# CH32V103R-R1-1v1.net
KiCad netlist of a schematic drawn in Altium Designer
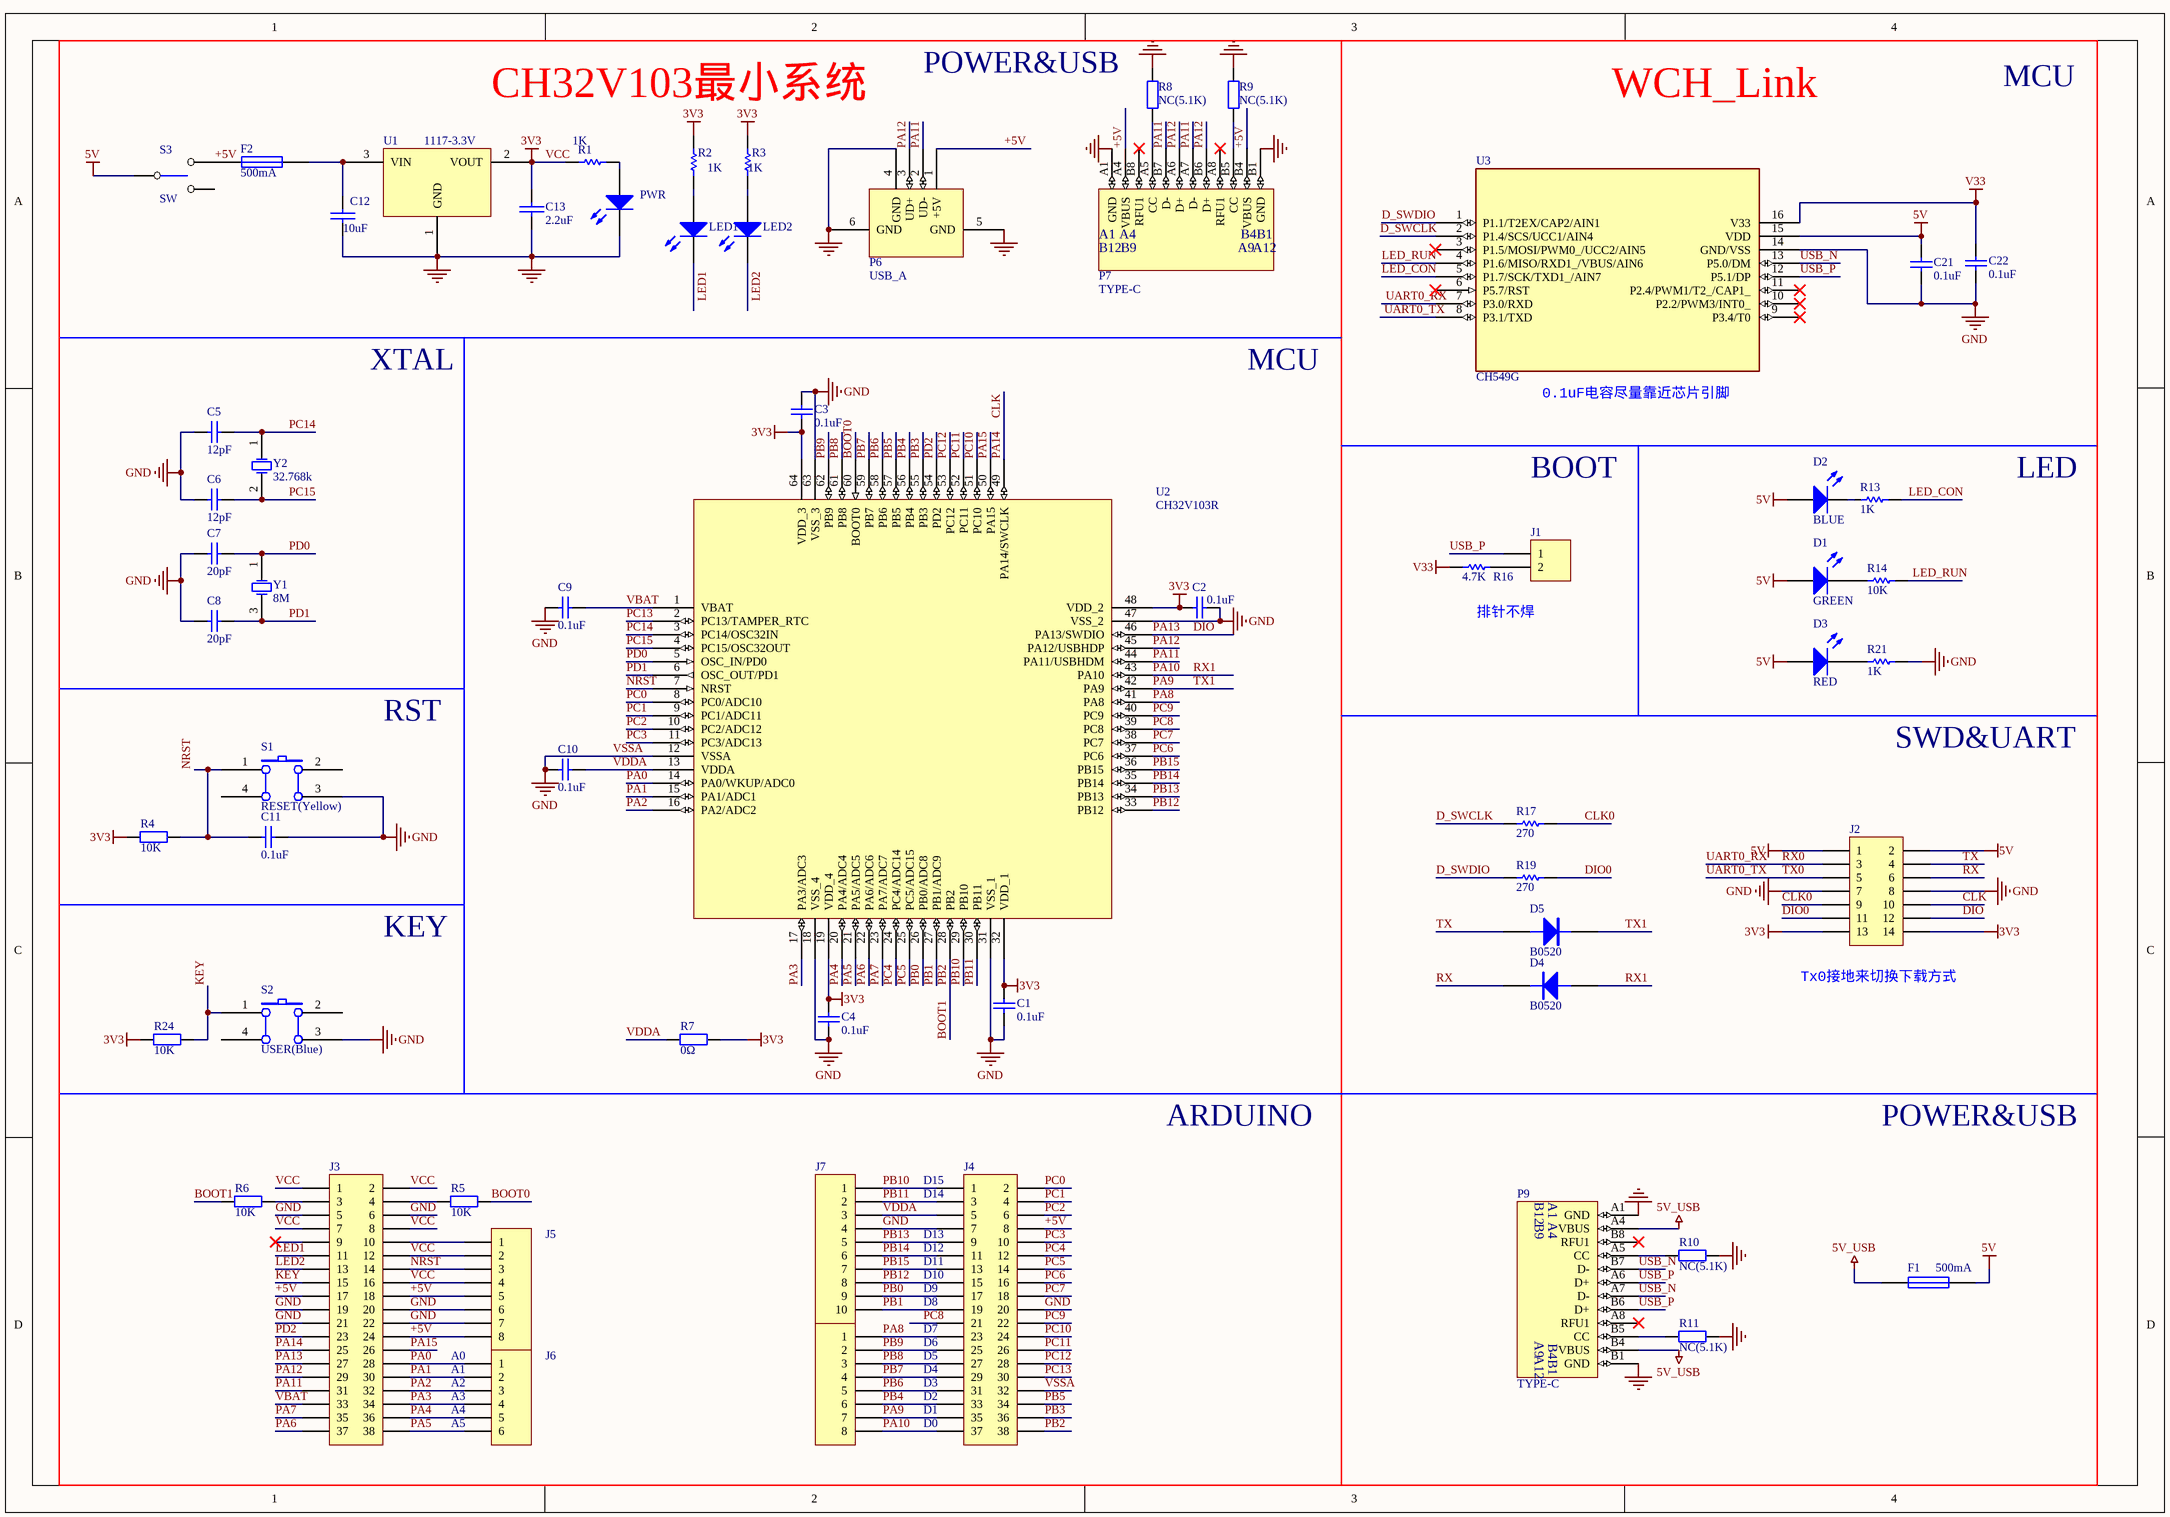
[diagram p0: CH32V103R-R1-1v1.SchDoc]

(export (version "E")
  (design (tool "Eeschema 10.0.6"))
  (components
    (comp (ref "C1")
      (value "0.1uF")
      (footprint "0603_C")
      (description "Capacitor")
      (libsource (lib "Miscellaneous Devices") (part "Cap"))
    )
    (comp (ref "C2")
      (value "0.1uF")
      (footprint "0603_C")
      (description "Capacitor")
      (libsource (lib "Miscellaneous Devices") (part "Cap"))
    )
    (comp (ref "C3")
      (value "0.1uF")
      (footprint "0603_C")
      (description "Capacitor")
      (libsource (lib "Miscellaneous Devices") (part "Cap"))
    )
    (comp (ref "C4")
      (value "0.1uF")
      (footprint "0603_C")
      (description "Capacitor")
      (libsource (lib "Miscellaneous Devices") (part "Cap"))
    )
    (comp (ref "C5")
      (value "12pF")
      (footprint "0603_C")
      (description "Capacitor")
      (libsource (lib "Miscellaneous Devices") (part "Cap"))
    )
    (comp (ref "C6")
      (value "12pF")
      (footprint "0603_C")
      (description "Capacitor")
      (libsource (lib "Miscellaneous Devices") (part "Cap"))
    )
    (comp (ref "C7")
      (value "20pF")
      (footprint "0603_C")
      (description "Capacitor")
      (libsource (lib "Miscellaneous Devices") (part "Cap"))
    )
    (comp (ref "C8")
      (value "20pF")
      (footprint "0603_C")
      (description "Capacitor")
      (libsource (lib "Miscellaneous Devices") (part "Cap"))
    )
    (comp (ref "C9")
      (value "0.1uF")
      (footprint "0603_C")
      (description "Capacitor")
      (libsource (lib "Miscellaneous Devices") (part "Cap"))
    )
    (comp (ref "C10")
      (value "0.1uF")
      (footprint "0603_C")
      (description "Capacitor")
      (libsource (lib "Miscellaneous Devices") (part "Cap"))
    )
    (comp (ref "C11")
      (value "0.1uF")
      (footprint "0603_C")
      (description "Capacitor")
      (libsource (lib "Miscellaneous Devices") (part "Cap"))
    )
    (comp (ref "C12")
      (value "10uF")
      (footprint "3216_C")
      (description "Capacitor")
      (libsource (lib "*") (part "CAP"))
    )
    (comp (ref "C13")
      (value "2.2uF")
      (footprint "0603_C")
      (description "Capacitor")
      (libsource (lib "*") (part "CAP"))
    )
    (comp (ref "C21")
      (value "0.1uF")
      (footprint "0603_C")
      (description "Capacitor")
      (fields (field (name "PUBLISHER") "Altium Limited"))
      (libsource (lib "MYLIB") (part "C-RAD-0603"))
    )
    (comp (ref "C22")
      (value "0.1uF")
      (footprint "0603_C")
      (description "Capacitor")
      (fields (field (name "PUBLISHER") "Altium Limited"))
      (libsource (lib "MYLIB") (part "C-RAD-0603"))
    )
    (comp (ref "D1")
      (value "GREEN")
      (footprint "0603+")
      (description "Typical RED, GREEN, YELLOW, AMBER GaAs LED")
      (fields (field (name "PUBLISHER") "Altium Limited"))
      (libsource (lib "MYLIB") (part "D0603"))
    )
    (comp (ref "D2")
      (value "BLUE")
      (footprint "0603+")
      (description "Typical RED, GREEN, YELLOW, AMBER GaAs LED")
      (fields (field (name "PUBLISHER") "Altium Limited"))
      (libsource (lib "MYLIB") (part "D0603"))
    )
    (comp (ref "D3")
      (value "RED")
      (footprint "0603+")
      (description "Typical RED, GREEN, YELLOW, AMBER GaAs LED")
      (fields (field (name "PUBLISHER") "Altium Limited"))
      (libsource (lib "MYLIB") (part "D0603"))
    )
    (comp (ref "D4")
      (value "B0520")
      (footprint "SOD-323")
      (description "Diode")
      (libsource (lib "*") (part "DIODE"))
    )
    (comp (ref "D5")
      (value "B0520")
      (footprint "SOD-323")
      (description "Diode")
      (libsource (lib "*") (part "DIODE"))
    )
    (comp (ref "F1")
      (value "500mA")
      (footprint "0805")
      (description "Fuse")
      (libsource (lib "*") (part "FUSE1"))
    )
    (comp (ref "F2")
      (value "500mA")
      (footprint "0805")
      (description "Fuse")
      (libsource (lib "*") (part "FUSE1"))
    )
    (comp (ref "J1")
      (value "Header 2")
      (footprint "SIP2-2.54MM")
      (description "Header, 2-Pin")
      (fields (field (name "PUBLISHER") "Altium Limited"))
      (libsource (lib "Miscellaneous Connectors") (part "Header 2"))
    )
    (comp (ref "J2")
      (value "Header 7X2")
      (footprint "IDC14-2.54mm")
      (description "Header, 7-Pin, Dual row")
      (fields (field (name "PUBLISHER") "Altium Limited"))
      (libsource (lib "Miscellaneous Connectors") (part "Header 7X2"))
    )
    (comp (ref "J3")
      (value "Header 19X2")
      (footprint "IDC38-2.54mm")
      (description "Header, 19-Pin, Dual row")
      (fields (field (name "PUBLISHER") "Altium Limited"))
      (libsource (lib "Miscellaneous Connectors") (part "Header 19X2"))
    )
    (comp (ref "J4")
      (value "Header 19X2")
      (footprint "IDC38-2.54mm")
      (description "Header, 19-Pin, Dual row")
      (fields (field (name "PUBLISHER") "Altium Limited"))
      (libsource (lib "Miscellaneous Connectors") (part "Header 19X2"))
    )
    (comp (ref "J5")
      (value "Header 8")
      (footprint "SIP8-2.54mm")
      (description "Header, 8-Pin")
      (fields (field (name "PUBLISHER") "Altium Limited"))
      (libsource (lib "") (part "Header 8_1"))
    )
    (comp (ref "J6")
      (value "Header 6")
      (footprint "SIP6-2.54MM")
      (description "Header, 6-Pin")
      (fields (field (name "PUBLISHER") "Altium Limited"))
      (libsource (lib "Miscellaneous Connectors") (part "Header 6"))
    )
    (comp (ref "J7")
      (value "Header 10")
      (footprint "SIP10-2.54mm")
      (description "Header, 10-Pin")
      (fields (field (name "PUBLISHER") "Altium Limited"))
      (libsource (lib "Miscellaneous Connectors") (part "Header 10"))
    )
    (comp (ref "J8")
      (value "Header 8")
      (footprint "SIP8-2.54mm")
      (description "Header, 8-Pin")
      (fields (field (name "PUBLISHER") "Altium Limited"))
      (libsource (lib "Miscellaneous Connectors") (part "Header 8"))
    )
    (comp (ref "LED1")
      (value "LED1   blue")
      (footprint "0603+")
      (description "Typical INFRARED GaAs LED")
      (fields (field (name "PUBLISHER") "Altium Limited"))
      (libsource (lib "Miscellaneous Devices") (part "LED0"))
    )
    (comp (ref "LED2")
      (value "LED2  blue")
      (footprint "0603+")
      (description "Typical INFRARED GaAs LED")
      (fields (field (name "PUBLISHER") "Altium Limited"))
      (libsource (lib "Miscellaneous Devices") (part "LED0"))
    )
    (comp (ref "P6")
      (value "USB_A")
      (footprint "USBAF")
      (description "USB Port")
      (libsource (lib "CHXXXSCH") (part "USB"))
    )
    (comp (ref "P7")
      (value "TYPE-C")
      (footprint "TYPE-C-Receptacle-2.0")
      (libsource (lib "") (part "TYPE-C1_1"))
    )
    (comp (ref "P9")
      (value "TYPE-C")
      (footprint "TYPE-C-Receptacle-2.0")
      (libsource (lib "*") (part "TYPE-C1"))
    )
    (comp (ref "PWR")
      (value "POWER  red")
      (footprint "0603+")
      (description "Typical INFRARED GaAs LED")
      (fields (field (name "PUBLISHER") "Altium Limited"))
      (libsource (lib "Miscellaneous Devices") (part "LED0"))
    )
    (comp (ref "R1")
      (value "1K")
      (footprint "0603")
      (description "Semiconductor Resistor")
      (libsource (lib "Miscellaneous Devices") (part "Res Semi"))
    )
    (comp (ref "R2")
      (value "1K")
      (footprint "0603")
      (description "Semiconductor Resistor")
      (libsource (lib "Miscellaneous Devices") (part "Res Semi"))
    )
    (comp (ref "R3")
      (value "1K")
      (footprint "0603")
      (description "Semiconductor Resistor")
      (libsource (lib "Miscellaneous Devices") (part "Res Semi"))
    )
    (comp (ref "R4")
      (value "10K")
      (footprint "0603")
      (description "Resistor")
      (libsource (lib "") (part "Res2_2"))
    )
    (comp (ref "R5")
      (value "10K")
      (footprint "0603")
      (description "Resistor")
      (libsource (lib "Miscellaneous Devices") (part "Res2"))
    )
    (comp (ref "R6")
      (value "10K")
      (footprint "0603")
      (description "Resistor")
      (libsource (lib "Miscellaneous Devices") (part "Res2"))
    )
    (comp (ref "R7")
      (value "0Ω")
      (footprint "0603")
      (description "Resistor")
      (libsource (lib "") (part "Res2_2"))
    )
    (comp (ref "R8")
      (value "NC(5.1K)")
      (footprint "0603")
      (description "Resistor")
      (libsource (lib "") (part "Res2_1"))
    )
    (comp (ref "R9")
      (value "NC(5.1K)")
      (footprint "0603")
      (description "Resistor")
      (libsource (lib "") (part "Res2_1"))
    )
    (comp (ref "R10")
      (value "NC(5.1K)")
      (footprint "0603")
      (description "Resistor")
      (libsource (lib "Miscellaneous Devices") (part "Res2"))
    )
    (comp (ref "R11")
      (value "NC(5.1K)")
      (footprint "0603")
      (description "Resistor")
      (libsource (lib "Miscellaneous Devices") (part "Res2"))
    )
    (comp (ref "R13")
      (value "1K")
      (footprint "0603")
      (description "Resistor")
      (fields (field (name "PUBLISHER") "Altium Limited"))
      (libsource (lib "MYLIB") (part "0603-1"))
    )
    (comp (ref "R14")
      (value "10K")
      (footprint "0603")
      (description "Resistor")
      (fields (field (name "PUBLISHER") "Altium Limited"))
      (libsource (lib "MYLIB") (part "0603-1"))
    )
    (comp (ref "R16")
      (value "4.7K")
      (footprint "0603")
      (description "Resistor")
      (fields (field (name "PUBLISHER") "Altium Limited"))
      (libsource (lib "MYLIB") (part "0603-1"))
    )
    (comp (ref "R17")
      (value "270")
      (footprint "0603")
      (description "Resistor")
      (fields (field (name "PUBLISHER") "Altium Limited"))
      (libsource (lib "MYLIB") (part "0603-1"))
    )
    (comp (ref "R19")
      (value "270")
      (footprint "0603")
      (description "Resistor")
      (fields (field (name "PUBLISHER") "Altium Limited"))
      (libsource (lib "MYLIB") (part "0603-1"))
    )
    (comp (ref "R21")
      (value "1K")
      (footprint "0603")
      (description "Resistor")
      (fields (field (name "PUBLISHER") "Altium Limited"))
      (libsource (lib "MYLIB") (part "0603-1"))
    )
    (comp (ref "R24")
      (value "10K")
      (footprint "0603")
      (description "Resistor")
      (libsource (lib "") (part "Res2_2"))
    )
    (comp (ref "S1")
      (value "RESET(Yellow)")
      (footprint "KEYX")
      (description "SE PUSHBUTTON")
      (libsource (lib "Documents") (part "SW PUSHBUTTON"))
    )
    (comp (ref "S2")
      (value "USER(Blue)")
      (footprint "KEYX")
      (description "SE PUSHBUTTON")
      (libsource (lib "Documents") (part "SW PUSHBUTTON"))
    )
    (comp (ref "S3") (value "SW") (footprint "KEY2") (libsource (lib "MYSCH") (part "SW")))
    (comp (ref "U1")
      (value "1117-3.3V")
      (footprint "SOT-223")
      (libsource (lib "wch_sch_others") (part "1117-3.3V"))
    )
    (comp (ref "U2")
      (value "CH32V103R")
      (footprint "LQFP64M_10X10")
      (description "RISC-V MCU with USB device & USB host & ADC & Touch Key")
      (libsource (lib "CHXXX(1)") (part "CH32V103R"))
    )
    (comp (ref "U3")
      (value "CH549G")
      (footprint "SOP16")
      (description "8bit MCS51 MCU with ADC & USB type-C host & device & dual UART & SPI")
      (libsource (lib "CHXXXSCH(1)") (part "CH549G"))
    )
    (comp (ref "Y1")
      (value "8M")
      (footprint "XT3225")
      (description "Crystal Oscillator")
      (fields (field (name "PUBLISHER") "Altium Limited"))
      (libsource (lib "Miscellaneous Devices") (part "XTAL"))
    )
    (comp (ref "Y2")
      (value "32.768k")
      (footprint "FC-135")
      (description "Crystal Oscillator")
      (fields (field (name "PUBLISHER") "Altium Limited"))
      (libsource (lib "") (part "XTAL_1"))
    )
  )
  (nets
    (net (code "1") (name "/+5V") (class "Default")
      (node (ref "F2") (pin "1") (pinfunction "1_1") (pintype "passive"))
      (node (ref "J3") (pin "17") (pinfunction "17_17") (pintype "passive"))
      (node (ref "J3") (pin "18") (pinfunction "18_18") (pintype "passive"))
      (node (ref "J3") (pin "24") (pinfunction "24_24") (pintype "passive"))
      (node (ref "J4") (pin "8") (pinfunction "8_8") (pintype "passive"))
      (node (ref "J5") (pin "5") (pinfunction "5_5") (pintype "passive"))
      (node (ref "J5") (pin "8") (pinfunction "8_8") (pintype "passive"))
      (node (ref "P6") (pin "1") (pinfunction "+5V_1") (pintype "power_in"))
      (node (ref "P7") (pin "A4") (pinfunction "VBUS_A4") (pintype "bidirectional"))
      (node (ref "P7") (pin "B4") (pinfunction "VBUS_B4") (pintype "bidirectional"))
      (node (ref "S3") (pin "3") (pinfunction "3_3") (pintype "passive"))
    )
    (net (code "3") (name "/BOOT0") (class "Default")
      (node (ref "R5") (pin "2") (pinfunction "2_2") (pintype "passive"))
      (node (ref "U2") (pin "60") (pinfunction "BOOT0_60") (pintype "input"))
    )
    (net (code "4") (name "/BOOT1") (class "Default")
      (node (ref "J4") (pin "38") (pinfunction "38_38") (pintype "passive"))
      (node (ref "R6") (pin "1") (pinfunction "1_1") (pintype "passive"))
      (node (ref "U2") (pin "28") (pinfunction "PB2_28") (pintype "bidirectional"))
    )
    (net (code "5") (name "/CLK") (class "Default")
      (node (ref "J2") (pin "10") (pinfunction "10_10") (pintype "passive"))
      (node (ref "J3") (pin "25") (pinfunction "25_25") (pintype "passive"))
      (node (ref "U2") (pin "49") (pinfunction "PA14/SWCLK_49") (pintype "bidirectional"))
    )
    (net (code "6") (name "/CLK0") (class "Default")
      (node (ref "J2") (pin "9") (pinfunction "9_9") (pintype "passive"))
      (node (ref "R17") (pin "1") (pinfunction "1_1") (pintype "passive"))
    )
    (net (code "7") (name "/DIO") (class "Default")
      (node (ref "J2") (pin "12") (pinfunction "12_12") (pintype "passive"))
      (node (ref "J3") (pin "27") (pinfunction "27_27") (pintype "passive"))
      (node (ref "U2") (pin "46") (pinfunction "PA13/SWDIO_46") (pintype "bidirectional"))
    )
    (net (code "8") (name "/DIO0") (class "Default")
      (node (ref "J2") (pin "11") (pinfunction "11_11") (pintype "passive"))
      (node (ref "R19") (pin "1") (pinfunction "1_1") (pintype "passive"))
    )
    (net (code "9") (name "/D_SWCLK") (class "Default")
      (node (ref "R17") (pin "2") (pinfunction "2_2") (pintype "passive"))
      (node (ref "U3") (pin "2") (pinfunction "P1.4/SCS/UCC1/AIN4_2") (pintype "bidirectional"))
    )
    (net (code "10") (name "/D_SWDIO") (class "Default")
      (node (ref "R19") (pin "2") (pinfunction "2_2") (pintype "passive"))
      (node (ref "U3") (pin "1") (pinfunction "P1.1/T2EX/CAP2/AIN1_1") (pintype "bidirectional"))
    )
    (net (code "11") (name "/KEY") (class "Default")
      (node (ref "J3") (pin "15") (pinfunction "15_15") (pintype "passive"))
      (node (ref "R24") (pin "1") (pinfunction "1_1") (pintype "passive"))
      (node (ref "S2") (pin "1") (pinfunction "A0_1") (pintype "passive"))
    )
    (net (code "12") (name "/LED1") (class "Default")
      (node (ref "J3") (pin "11") (pinfunction "11_11") (pintype "passive"))
      (node (ref "LED1") (pin "2") (pinfunction "K_2") (pintype "passive"))
    )
    (net (code "13") (name "/LED2") (class "Default")
      (node (ref "J3") (pin "13") (pinfunction "13_13") (pintype "passive"))
      (node (ref "LED2") (pin "2") (pinfunction "K_2") (pintype "passive"))
    )
    (net (code "14") (name "/LED_CON") (class "Default")
      (node (ref "R13") (pin "1") (pinfunction "1_1") (pintype "passive"))
      (node (ref "U3") (pin "5") (pinfunction "P1.7/SCK/TXD1_/AIN7_5") (pintype "bidirectional"))
    )
    (net (code "15") (name "/LED_RUN") (class "Default")
      (node (ref "R14") (pin "1") (pinfunction "1_1") (pintype "passive"))
      (node (ref "U3") (pin "4") (pinfunction "P1.6/MISO/RXD1_/VBUS/AIN6_4") (pintype "bidirectional"))
    )
    (net (code "16") (name "/NRST") (class "Default")
      (node (ref "C11") (pin "2") (pinfunction "2_2") (pintype "passive"))
      (node (ref "J3") (pin "14") (pinfunction "14_14") (pintype "passive"))
      (node (ref "J5") (pin "3") (pinfunction "3_3") (pintype "passive"))
      (node (ref "R4") (pin "1") (pinfunction "1_1") (pintype "passive"))
      (node (ref "S1") (pin "1") (pinfunction "A0_1") (pintype "passive"))
      (node (ref "U2") (pin "7") (pinfunction "NRST_7") (pintype "input"))
    )
    (net (code "17") (name "/PA0") (class "Default")
      (node (ref "J3") (pin "28") (pinfunction "28_28") (pintype "passive"))
      (node (ref "J6") (pin "1") (pinfunction "1_1") (pintype "passive"))
      (node (ref "U2") (pin "14") (pinfunction "PA0/WKUP/ADC0_14") (pintype "bidirectional"))
    )
    (net (code "18") (name "/PA1") (class "Default")
      (node (ref "J3") (pin "30") (pinfunction "30_30") (pintype "passive"))
      (node (ref "J6") (pin "2") (pinfunction "2_2") (pintype "passive"))
      (node (ref "U2") (pin "15") (pinfunction "PA1/ADC1_15") (pintype "bidirectional"))
    )
    (net (code "19") (name "/PA2") (class "Default")
      (node (ref "J3") (pin "32") (pinfunction "32_32") (pintype "passive"))
      (node (ref "J6") (pin "3") (pinfunction "3_3") (pintype "passive"))
      (node (ref "U2") (pin "16") (pinfunction "PA2/ADC2_16") (pintype "bidirectional"))
    )
    (net (code "20") (name "/PA3") (class "Default")
      (node (ref "J3") (pin "34") (pinfunction "34_34") (pintype "passive"))
      (node (ref "J6") (pin "4") (pinfunction "4_4") (pintype "passive"))
      (node (ref "U2") (pin "17") (pinfunction "PA3/ADC3_17") (pintype "bidirectional"))
    )
    (net (code "21") (name "/PA4") (class "Default")
      (node (ref "J3") (pin "36") (pinfunction "36_36") (pintype "passive"))
      (node (ref "J6") (pin "5") (pinfunction "5_5") (pintype "passive"))
      (node (ref "U2") (pin "20") (pinfunction "PA4/ADC4_20") (pintype "bidirectional"))
    )
    (net (code "22") (name "/PA5") (class "Default")
      (node (ref "J3") (pin "38") (pinfunction "38_38") (pintype "passive"))
      (node (ref "J6") (pin "6") (pinfunction "6_6") (pintype "passive"))
      (node (ref "U2") (pin "21") (pinfunction "PA5/ADC5_21") (pintype "bidirectional"))
    )
    (net (code "23") (name "/PA6") (class "Default")
      (node (ref "J3") (pin "37") (pinfunction "37_37") (pintype "passive"))
      (node (ref "U2") (pin "22") (pinfunction "PA6/ADC6_22") (pintype "bidirectional"))
    )
    (net (code "24") (name "/PA7") (class "Default")
      (node (ref "J3") (pin "35") (pinfunction "35_35") (pintype "passive"))
      (node (ref "U2") (pin "23") (pinfunction "PA7/ADC7_23") (pintype "bidirectional"))
    )
    (net (code "25") (name "/PA8") (class "Default")
      (node (ref "J4") (pin "23") (pinfunction "23_23") (pintype "passive"))
      (node (ref "J8") (pin "1") (pinfunction "1_1") (pintype "passive"))
      (node (ref "U2") (pin "41") (pinfunction "PA8_41") (pintype "bidirectional"))
    )
    (net (code "26") (name "/PA9") (class "Default")
      (node (ref "D5") (pin "2") (pinfunction "K_2") (pintype "passive"))
      (node (ref "J4") (pin "35") (pinfunction "35_35") (pintype "passive"))
      (node (ref "J8") (pin "7") (pinfunction "7_7") (pintype "passive"))
      (node (ref "U2") (pin "42") (pinfunction "PA9_42") (pintype "bidirectional"))
    )
    (net (code "27") (name "/PA10") (class "Default")
      (node (ref "D4") (pin "1") (pinfunction "A_1") (pintype "passive"))
      (node (ref "J4") (pin "37") (pinfunction "37_37") (pintype "passive"))
      (node (ref "J8") (pin "8") (pinfunction "8_8") (pintype "passive"))
      (node (ref "U2") (pin "43") (pinfunction "PA10_43") (pintype "bidirectional"))
    )
    (net (code "28") (name "/PA11") (class "Default")
      (node (ref "J3") (pin "31") (pinfunction "31_31") (pintype "passive"))
      (node (ref "P6") (pin "2") (pinfunction "UD-_2") (pintype "bidirectional"))
      (node (ref "P7") (pin "A7") (pinfunction "D-_A7") (pintype "bidirectional"))
      (node (ref "P7") (pin "B7") (pinfunction "D-_B7") (pintype "bidirectional"))
      (node (ref "U2") (pin "44") (pinfunction "PA11/USBHDM_44") (pintype "bidirectional"))
    )
    (net (code "29") (name "/PA12") (class "Default")
      (node (ref "J3") (pin "29") (pinfunction "29_29") (pintype "passive"))
      (node (ref "P6") (pin "3") (pinfunction "UD+_3") (pintype "bidirectional"))
      (node (ref "P7") (pin "A6") (pinfunction "D+_A6") (pintype "bidirectional"))
      (node (ref "P7") (pin "B6") (pinfunction "D+_B6") (pintype "bidirectional"))
      (node (ref "U2") (pin "45") (pinfunction "PA12/USBHDP_45") (pintype "bidirectional"))
    )
    (net (code "30") (name "/PA15") (class "Default")
      (node (ref "J3") (pin "26") (pinfunction "26_26") (pintype "passive"))
      (node (ref "U2") (pin "50") (pinfunction "PA15_50") (pintype "bidirectional"))
    )
    (net (code "31") (name "/PB0") (class "Default")
      (node (ref "J4") (pin "17") (pinfunction "17_17") (pintype "passive"))
      (node (ref "J7") (pin "9") (pinfunction "9_9") (pintype "passive"))
      (node (ref "U2") (pin "26") (pinfunction "PB0/ADC8_26") (pintype "bidirectional"))
    )
    (net (code "32") (name "/PB1") (class "Default")
      (node (ref "J4") (pin "19") (pinfunction "19_19") (pintype "passive"))
      (node (ref "J7") (pin "10") (pinfunction "10_10") (pintype "passive"))
      (node (ref "U2") (pin "27") (pinfunction "PB1/ADC9_27") (pintype "bidirectional"))
    )
    (net (code "33") (name "/PB3") (class "Default")
      (node (ref "J4") (pin "36") (pinfunction "36_36") (pintype "passive"))
      (node (ref "U2") (pin "55") (pinfunction "PB3_55") (pintype "bidirectional"))
    )
    (net (code "34") (name "/PB4") (class "Default")
      (node (ref "J4") (pin "33") (pinfunction "33_33") (pintype "passive"))
      (node (ref "J8") (pin "6") (pinfunction "6_6") (pintype "passive"))
      (node (ref "U2") (pin "56") (pinfunction "PB4_56") (pintype "bidirectional"))
    )
    (net (code "35") (name "/PB5") (class "Default")
      (node (ref "J4") (pin "34") (pinfunction "34_34") (pintype "passive"))
      (node (ref "U2") (pin "57") (pinfunction "PB5_57") (pintype "bidirectional"))
    )
    (net (code "36") (name "/PB6") (class "Default")
      (node (ref "J4") (pin "31") (pinfunction "31_31") (pintype "passive"))
      (node (ref "J8") (pin "5") (pinfunction "5_5") (pintype "passive"))
      (node (ref "U2") (pin "58") (pinfunction "PB6_58") (pintype "bidirectional"))
    )
    (net (code "37") (name "/PB7") (class "Default")
      (node (ref "J4") (pin "29") (pinfunction "29_29") (pintype "passive"))
      (node (ref "J8") (pin "4") (pinfunction "4_4") (pintype "passive"))
      (node (ref "U2") (pin "59") (pinfunction "PB7_59") (pintype "bidirectional"))
    )
    (net (code "38") (name "/PB8") (class "Default")
      (node (ref "J4") (pin "27") (pinfunction "27_27") (pintype "passive"))
      (node (ref "J8") (pin "3") (pinfunction "3_3") (pintype "passive"))
      (node (ref "U2") (pin "61") (pinfunction "PB8_61") (pintype "bidirectional"))
    )
    (net (code "39") (name "/PB9") (class "Default")
      (node (ref "J4") (pin "25") (pinfunction "25_25") (pintype "passive"))
      (node (ref "J8") (pin "2") (pinfunction "2_2") (pintype "passive"))
      (node (ref "U2") (pin "62") (pinfunction "PB9_62") (pintype "bidirectional"))
    )
    (net (code "40") (name "/PB10") (class "Default")
      (node (ref "J4") (pin "1") (pinfunction "1_1") (pintype "passive"))
      (node (ref "J7") (pin "1") (pinfunction "1_1") (pintype "passive"))
      (node (ref "U2") (pin "29") (pinfunction "PB10_29") (pintype "bidirectional"))
    )
    (net (code "41") (name "/PB11") (class "Default")
      (node (ref "J4") (pin "3") (pinfunction "3_3") (pintype "passive"))
      (node (ref "J7") (pin "2") (pinfunction "2_2") (pintype "passive"))
      (node (ref "U2") (pin "30") (pinfunction "PB11_30") (pintype "bidirectional"))
    )
    (net (code "42") (name "/PB12") (class "Default")
      (node (ref "J4") (pin "15") (pinfunction "15_15") (pintype "passive"))
      (node (ref "J7") (pin "8") (pinfunction "8_8") (pintype "passive"))
      (node (ref "U2") (pin "33") (pinfunction "PB12_33") (pintype "bidirectional"))
    )
    (net (code "43") (name "/PB13") (class "Default")
      (node (ref "J4") (pin "9") (pinfunction "9_9") (pintype "passive"))
      (node (ref "J7") (pin "5") (pinfunction "5_5") (pintype "passive"))
      (node (ref "U2") (pin "34") (pinfunction "PB13_34") (pintype "bidirectional"))
    )
    (net (code "44") (name "/PB14") (class "Default")
      (node (ref "J4") (pin "11") (pinfunction "11_11") (pintype "passive"))
      (node (ref "J7") (pin "6") (pinfunction "6_6") (pintype "passive"))
      (node (ref "U2") (pin "35") (pinfunction "PB14_35") (pintype "bidirectional"))
    )
    (net (code "45") (name "/PB15") (class "Default")
      (node (ref "J4") (pin "13") (pinfunction "13_13") (pintype "passive"))
      (node (ref "J7") (pin "7") (pinfunction "7_7") (pintype "passive"))
      (node (ref "U2") (pin "36") (pinfunction "PB15_36") (pintype "bidirectional"))
    )
    (net (code "46") (name "/PC0") (class "Default")
      (node (ref "J4") (pin "2") (pinfunction "2_2") (pintype "passive"))
      (node (ref "U2") (pin "8") (pinfunction "PC0/ADC10_8") (pintype "bidirectional"))
    )
    (net (code "47") (name "/PC1") (class "Default")
      (node (ref "J4") (pin "4") (pinfunction "4_4") (pintype "passive"))
      (node (ref "U2") (pin "9") (pinfunction "PC1/ADC11_9") (pintype "bidirectional"))
    )
    (net (code "48") (name "/PC2") (class "Default")
      (node (ref "J4") (pin "6") (pinfunction "6_6") (pintype "passive"))
      (node (ref "U2") (pin "10") (pinfunction "PC2/ADC12_10") (pintype "bidirectional"))
    )
    (net (code "49") (name "/PC3") (class "Default")
      (node (ref "J4") (pin "10") (pinfunction "10_10") (pintype "passive"))
      (node (ref "U2") (pin "11") (pinfunction "PC3/ADC13_11") (pintype "bidirectional"))
    )
    (net (code "50") (name "/PC4") (class "Default")
      (node (ref "J4") (pin "12") (pinfunction "12_12") (pintype "passive"))
      (node (ref "U2") (pin "24") (pinfunction "PC4/ADC14_24") (pintype "bidirectional"))
    )
    (net (code "51") (name "/PC5") (class "Default")
      (node (ref "J4") (pin "14") (pinfunction "14_14") (pintype "passive"))
      (node (ref "U2") (pin "25") (pinfunction "PC5/ADC15_25") (pintype "bidirectional"))
    )
    (net (code "52") (name "/PC6") (class "Default")
      (node (ref "J4") (pin "16") (pinfunction "16_16") (pintype "passive"))
      (node (ref "U2") (pin "37") (pinfunction "PC6_37") (pintype "bidirectional"))
    )
    (net (code "53") (name "/PC7") (class "Default")
      (node (ref "J4") (pin "18") (pinfunction "18_18") (pintype "passive"))
      (node (ref "U2") (pin "38") (pinfunction "PC7_38") (pintype "bidirectional"))
    )
    (net (code "54") (name "/PC8") (class "Default")
      (node (ref "J4") (pin "21") (pinfunction "21_21") (pintype "passive"))
      (node (ref "U2") (pin "39") (pinfunction "PC8_39") (pintype "bidirectional"))
    )
    (net (code "55") (name "/PC9") (class "Default")
      (node (ref "J4") (pin "22") (pinfunction "22_22") (pintype "passive"))
      (node (ref "U2") (pin "40") (pinfunction "PC9_40") (pintype "bidirectional"))
    )
    (net (code "56") (name "/PC10") (class "Default")
      (node (ref "J4") (pin "24") (pinfunction "24_24") (pintype "passive"))
      (node (ref "U2") (pin "51") (pinfunction "PC10_51") (pintype "bidirectional"))
    )
    (net (code "57") (name "/PC11") (class "Default")
      (node (ref "J4") (pin "26") (pinfunction "26_26") (pintype "passive"))
      (node (ref "U2") (pin "52") (pinfunction "PC11_52") (pintype "bidirectional"))
    )
    (net (code "58") (name "/PC12") (class "Default")
      (node (ref "J4") (pin "28") (pinfunction "28_28") (pintype "passive"))
      (node (ref "U2") (pin "53") (pinfunction "PC12_53") (pintype "bidirectional"))
    )
    (net (code "59") (name "/PC13") (class "Default")
      (node (ref "J4") (pin "30") (pinfunction "30_30") (pintype "passive"))
      (node (ref "U2") (pin "2") (pinfunction "PC13/TAMPER_RTC_2") (pintype "bidirectional"))
    )
    (net (code "60") (name "/PC14") (class "Default")
      (node (ref "C5") (pin "1") (pinfunction "1_1") (pintype "passive"))
      (node (ref "U2") (pin "3") (pinfunction "PC14/OSC32IN_3") (pintype "bidirectional"))
      (node (ref "Y2") (pin "1") (pinfunction "OSC1_1") (pintype "passive"))
    )
    (net (code "61") (name "/PC15") (class "Default")
      (node (ref "C6") (pin "1") (pinfunction "1_1") (pintype "passive"))
      (node (ref "U2") (pin "4") (pinfunction "PC15/OSC32OUT_4") (pintype "bidirectional"))
      (node (ref "Y2") (pin "2") (pinfunction "OSC2_2") (pintype "passive"))
    )
    (net (code "62") (name "/PD0") (class "Default")
      (node (ref "C7") (pin "2") (pinfunction "2_2") (pintype "passive"))
      (node (ref "U2") (pin "5") (pinfunction "OSC_IN/PD0_5") (pintype "input"))
      (node (ref "Y1") (pin "1") (pinfunction "OSC1_1") (pintype "passive"))
    )
    (net (code "63") (name "/PD1") (class "Default")
      (node (ref "C8") (pin "2") (pinfunction "2_2") (pintype "passive"))
      (node (ref "U2") (pin "6") (pinfunction "OSC_OUT/PD1_6") (pintype "output"))
      (node (ref "Y1") (pin "3") (pinfunction "OSC2_3") (pintype "passive"))
    )
    (net (code "64") (name "/PD2") (class "Default")
      (node (ref "J3") (pin "23") (pinfunction "23_23") (pintype "passive"))
      (node (ref "U2") (pin "54") (pinfunction "PD2_54") (pintype "bidirectional"))
    )
    (net (code "65") (name "/RX") (class "Default")
      (node (ref "D4") (pin "2") (pinfunction "K_2") (pintype "passive"))
      (node (ref "J2") (pin "6") (pinfunction "6_6") (pintype "passive"))
    )
    (net (code "66") (name "/RX0") (class "Default")
      (node (ref "J2") (pin "3") (pinfunction "3_3") (pintype "passive"))
      (node (ref "U3") (pin "7") (pinfunction "P3.0/RXD_7") (pintype "bidirectional"))
    )
    (net (code "67") (name "/TX") (class "Default")
      (node (ref "D5") (pin "1") (pinfunction "A_1") (pintype "passive"))
      (node (ref "J2") (pin "4") (pinfunction "4_4") (pintype "passive"))
    )
    (net (code "68") (name "/TX0") (class "Default")
      (node (ref "J2") (pin "5") (pinfunction "5_5") (pintype "passive"))
      (node (ref "U3") (pin "8") (pinfunction "P3.1/TXD_8") (pintype "bidirectional"))
    )
    (net (code "69") (name "/USB_N") (class "Default")
      (node (ref "P9") (pin "A7") (pinfunction "D-_A7") (pintype "bidirectional"))
      (node (ref "P9") (pin "B7") (pinfunction "D-_B7") (pintype "bidirectional"))
      (node (ref "U3") (pin "13") (pinfunction "P5.0/DM_13") (pintype "bidirectional"))
    )
    (net (code "70") (name "/USB_P") (class "Default")
      (node (ref "J1") (pin "1") (pinfunction "1_1") (pintype "passive"))
      (node (ref "P9") (pin "A6") (pinfunction "D+_A6") (pintype "bidirectional"))
      (node (ref "P9") (pin "B6") (pinfunction "D+_B6") (pintype "bidirectional"))
      (node (ref "U3") (pin "12") (pinfunction "P5.1/DP_12") (pintype "bidirectional"))
    )
    (net (code "71") (name "/VBAT") (class "Default")
      (node (ref "C9") (pin "1") (pinfunction "1_1") (pintype "passive"))
      (node (ref "J3") (pin "33") (pinfunction "33_33") (pintype "passive"))
      (node (ref "U2") (pin "1") (pinfunction "VBAT_1") (pintype "power_in"))
    )
    (net (code "72") (name "/VDDA") (class "Default")
      (node (ref "C10") (pin "1") (pinfunction "1_1") (pintype "passive"))
      (node (ref "J4") (pin "5") (pinfunction "5_5") (pintype "passive"))
      (node (ref "J7") (pin "3") (pinfunction "3_3") (pintype "passive"))
      (node (ref "R7") (pin "2") (pinfunction "2_2") (pintype "passive"))
      (node (ref "U2") (pin "13") (pinfunction "VDDA_13") (pintype "power_in"))
    )
    (net (code "73") (name "3V3") (class "Default")
      (node (ref "C1") (pin "2") (pinfunction "2_2") (pintype "passive"))
      (node (ref "C13") (pin "1") (pinfunction "1_1") (pintype "passive"))
      (node (ref "C2") (pin "2") (pinfunction "2_2") (pintype "passive"))
      (node (ref "C3") (pin "2") (pinfunction "2_2") (pintype "passive"))
      (node (ref "C4") (pin "2") (pinfunction "2_2") (pintype "passive"))
      (node (ref "J2") (pin "13") (pinfunction "13_13") (pintype "passive"))
      (node (ref "J2") (pin "14") (pinfunction "14_14") (pintype "passive"))
      (node (ref "J3") (pin "1") (pinfunction "1_1") (pintype "passive"))
      (node (ref "J3") (pin "12") (pinfunction "12_12") (pintype "passive"))
      (node (ref "J3") (pin "16") (pinfunction "16_16") (pintype "passive"))
      (node (ref "J3") (pin "2") (pinfunction "2_2") (pintype "passive"))
      (node (ref "J3") (pin "7") (pinfunction "7_7") (pintype "passive"))
      (node (ref "J3") (pin "8") (pinfunction "8_8") (pintype "passive"))
      (node (ref "J5") (pin "2") (pinfunction "2_2") (pintype "passive"))
      (node (ref "J5") (pin "4") (pinfunction "4_4") (pintype "passive"))
      (node (ref "R1") (pin "2") (pinfunction "2_2") (pintype "passive"))
      (node (ref "R2") (pin "1") (pinfunction "1_1") (pintype "passive"))
      (node (ref "R24") (pin "2") (pinfunction "2_2") (pintype "passive"))
      (node (ref "R3") (pin "1") (pinfunction "1_1") (pintype "passive"))
      (node (ref "R4") (pin "2") (pinfunction "2_2") (pintype "passive"))
      (node (ref "R7") (pin "1") (pinfunction "1_1") (pintype "passive"))
      (node (ref "U1") (pin "2") (pinfunction "VOUT_2") (pintype "passive"))
      (node (ref "U2") (pin "19") (pinfunction "VDD_4_19") (pintype "power_in"))
      (node (ref "U2") (pin "32") (pinfunction "VDD_1_32") (pintype "power_in"))
      (node (ref "U2") (pin "48") (pinfunction "VDD_2_48") (pintype "power_in"))
      (node (ref "U2") (pin "64") (pinfunction "VDD_3_64") (pintype "power_in"))
    )
    (net (code "74") (name "5V") (class "Default")
      (node (ref "C21") (pin "1") (pinfunction "1_1") (pintype "passive"))
      (node (ref "D1") (pin "1") (pinfunction "A_1") (pintype "passive"))
      (node (ref "D2") (pin "1") (pinfunction "A_1") (pintype "passive"))
      (node (ref "D3") (pin "1") (pinfunction "A_1") (pintype "passive"))
      (node (ref "F1") (pin "2") (pinfunction "2_2") (pintype "passive"))
      (node (ref "J2") (pin "1") (pinfunction "1_1") (pintype "passive"))
      (node (ref "J2") (pin "2") (pinfunction "2_2") (pintype "passive"))
      (node (ref "S3") (pin "1") (pinfunction "1_1") (pintype "passive"))
      (node (ref "U3") (pin "15") (pinfunction "VDD_15") (pintype "power_in"))
    )
    (net (code "75") (name "5V_USB") (class "Default")
      (node (ref "F1") (pin "1") (pinfunction "1_1") (pintype "passive"))
      (node (ref "P9") (pin "A4") (pinfunction "VBUS_A4") (pintype "bidirectional"))
      (node (ref "P9") (pin "B4") (pinfunction "VBUS_B4") (pintype "bidirectional"))
    )
    (net (code "76") (name "GND") (class "Default")
      (node (ref "C1") (pin "1") (pinfunction "1_1") (pintype "passive"))
      (node (ref "C10") (pin "2") (pinfunction "2_2") (pintype "passive"))
      (node (ref "C11") (pin "1") (pinfunction "1_1") (pintype "passive"))
      (node (ref "C12") (pin "2") (pinfunction "2_2") (pintype "passive"))
      (node (ref "C13") (pin "2") (pinfunction "2_2") (pintype "passive"))
      (node (ref "C2") (pin "1") (pinfunction "1_1") (pintype "passive"))
      (node (ref "C21") (pin "2") (pinfunction "2_2") (pintype "passive"))
      (node (ref "C22") (pin "2") (pinfunction "2_2") (pintype "passive"))
      (node (ref "C3") (pin "1") (pinfunction "1_1") (pintype "passive"))
      (node (ref "C4") (pin "1") (pinfunction "1_1") (pintype "passive"))
      (node (ref "C5") (pin "2") (pinfunction "2_2") (pintype "passive"))
      (node (ref "C6") (pin "2") (pinfunction "2_2") (pintype "passive"))
      (node (ref "C7") (pin "1") (pinfunction "1_1") (pintype "passive"))
      (node (ref "C8") (pin "1") (pinfunction "1_1") (pintype "passive"))
      (node (ref "C9") (pin "2") (pinfunction "2_2") (pintype "passive"))
      (node (ref "J2") (pin "7") (pinfunction "7_7") (pintype "passive"))
      (node (ref "J2") (pin "8") (pinfunction "8_8") (pintype "passive"))
      (node (ref "J3") (pin "19") (pinfunction "19_19") (pintype "passive"))
      (node (ref "J3") (pin "20") (pinfunction "20_20") (pintype "passive"))
      (node (ref "J3") (pin "21") (pinfunction "21_21") (pintype "passive"))
      (node (ref "J3") (pin "22") (pinfunction "22_22") (pintype "passive"))
      (node (ref "J3") (pin "5") (pinfunction "5_5") (pintype "passive"))
      (node (ref "J3") (pin "6") (pinfunction "6_6") (pintype "passive"))
      (node (ref "J4") (pin "20") (pinfunction "20_20") (pintype "passive"))
      (node (ref "J4") (pin "32") (pinfunction "32_32") (pintype "passive"))
      (node (ref "J4") (pin "7") (pinfunction "7_7") (pintype "passive"))
      (node (ref "J5") (pin "6") (pinfunction "6_6") (pintype "passive"))
      (node (ref "J5") (pin "7") (pinfunction "7_7") (pintype "passive"))
      (node (ref "J7") (pin "4") (pinfunction "4_4") (pintype "passive"))
      (node (ref "P6") (pin "4") (pinfunction "GND_4") (pintype "power_in"))
      (node (ref "P6") (pin "5") (pinfunction "GND_5") (pintype "power_in"))
      (node (ref "P6") (pin "6") (pinfunction "GND_6") (pintype "power_in"))
      (node (ref "P7") (pin "A1") (pinfunction "GND_A1") (pintype "bidirectional"))
      (node (ref "P7") (pin "B1") (pinfunction "GND_B1") (pintype "bidirectional"))
      (node (ref "P9") (pin "A1") (pinfunction "GND_A1") (pintype "bidirectional"))
      (node (ref "P9") (pin "B1") (pinfunction "GND_B1") (pintype "bidirectional"))
      (node (ref "PWR") (pin "2") (pinfunction "K_2") (pintype "passive"))
      (node (ref "R10") (pin "2") (pinfunction "2_2") (pintype "passive"))
      (node (ref "R11") (pin "2") (pinfunction "2_2") (pintype "passive"))
      (node (ref "R21") (pin "1") (pinfunction "1_1") (pintype "passive"))
      (node (ref "R8") (pin "1") (pinfunction "1_1") (pintype "passive"))
      (node (ref "R9") (pin "1") (pinfunction "1_1") (pintype "passive"))
      (node (ref "S1") (pin "3") (pinfunction "B1_3") (pintype "passive"))
      (node (ref "S2") (pin "3") (pinfunction "B1_3") (pintype "passive"))
      (node (ref "U1") (pin "1") (pinfunction "GND_1") (pintype "passive"))
      (node (ref "U2") (pin "12") (pinfunction "VSSA_12") (pintype "power_in"))
      (node (ref "U2") (pin "18") (pinfunction "VSS_4_18") (pintype "power_in"))
      (node (ref "U2") (pin "31") (pinfunction "VSS_1_31") (pintype "power_in"))
      (node (ref "U2") (pin "47") (pinfunction "VSS_2_47") (pintype "power_in"))
      (node (ref "U2") (pin "63") (pinfunction "VSS_3_63") (pintype "power_in"))
      (node (ref "U3") (pin "14") (pinfunction "GND/VSS_14") (pintype "power_in"))
    )
    (net (code "77") (name "Net-(D1-K)") (class "Default")
      (node (ref "D1") (pin "2") (pinfunction "K_2") (pintype "passive"))
      (node (ref "R14") (pin "2") (pinfunction "2_2") (pintype "passive"))
    )
    (net (code "78") (name "Net-(D2-K)") (class "Default")
      (node (ref "D2") (pin "2") (pinfunction "K_2") (pintype "passive"))
      (node (ref "R13") (pin "2") (pinfunction "2_2") (pintype "passive"))
    )
    (net (code "79") (name "Net-(D3-K)") (class "Default")
      (node (ref "D3") (pin "2") (pinfunction "K_2") (pintype "passive"))
      (node (ref "R21") (pin "2") (pinfunction "2_2") (pintype "passive"))
    )
    (net (code "80") (name "Net-(J1-Pad2)") (class "Default")
      (node (ref "J1") (pin "2") (pinfunction "2_2") (pintype "passive"))
      (node (ref "R16") (pin "1") (pinfunction "1_1") (pintype "passive"))
    )
    (net (code "81") (name "Net-(J3-Pad3)") (class "Default")
      (node (ref "J3") (pin "3") (pinfunction "3_3") (pintype "passive"))
      (node (ref "R6") (pin "2") (pinfunction "2_2") (pintype "passive"))
    )
    (net (code "82") (name "Net-(J3-Pad4)") (class "Default")
      (node (ref "J3") (pin "4") (pinfunction "4_4") (pintype "passive"))
      (node (ref "R5") (pin "1") (pinfunction "1_1") (pintype "passive"))
    )
    (net (code "83") (name "Net-(J3-Pad10)") (class "Default")
      (node (ref "J3") (pin "10") (pinfunction "10_10") (pintype "passive"))
      (node (ref "J5") (pin "1") (pinfunction "1_1") (pintype "passive"))
    )
    (net (code "84") (name "Net-(LED1-A)") (class "Default")
      (node (ref "LED1") (pin "1") (pinfunction "A_1") (pintype "passive"))
      (node (ref "R2") (pin "2") (pinfunction "2_2") (pintype "passive"))
    )
    (net (code "85") (name "Net-(LED2-A)") (class "Default")
      (node (ref "LED2") (pin "1") (pinfunction "A_1") (pintype "passive"))
      (node (ref "R3") (pin "2") (pinfunction "2_2") (pintype "passive"))
    )
    (net (code "86") (name "Net-(P7-CC-PadA5)") (class "Default")
      (node (ref "P7") (pin "A5") (pinfunction "CC_A5") (pintype "bidirectional"))
      (node (ref "R8") (pin "2") (pinfunction "2_2") (pintype "passive"))
    )
    (net (code "87") (name "Net-(P7-CC-PadB5)") (class "Default")
      (node (ref "P7") (pin "B5") (pinfunction "CC_B5") (pintype "bidirectional"))
      (node (ref "R9") (pin "2") (pinfunction "2_2") (pintype "passive"))
    )
    (net (code "88") (name "Net-(P9-CC-PadA5)") (class "Default")
      (node (ref "P9") (pin "A5") (pinfunction "CC_A5") (pintype "bidirectional"))
      (node (ref "R10") (pin "1") (pinfunction "1_1") (pintype "passive"))
    )
    (net (code "89") (name "Net-(P9-CC-PadB5)") (class "Default")
      (node (ref "P9") (pin "B5") (pinfunction "CC_B5") (pintype "bidirectional"))
      (node (ref "R11") (pin "1") (pinfunction "1_1") (pintype "passive"))
    )
    (net (code "90") (name "Net-(PWR-A)") (class "Default")
      (node (ref "PWR") (pin "1") (pinfunction "A_1") (pintype "passive"))
      (node (ref "R1") (pin "1") (pinfunction "1_1") (pintype "passive"))
    )
    (net (code "91") (name "Net-(U1-VIN)") (class "Default")
      (node (ref "C12") (pin "1") (pinfunction "1_1") (pintype "passive"))
      (node (ref "F2") (pin "2") (pinfunction "2_2") (pintype "passive"))
      (node (ref "U1") (pin "3") (pinfunction "VIN_3") (pintype "passive"))
    )
    (net (code "92") (name "V33") (class "Default")
      (node (ref "C22") (pin "1") (pinfunction "1_1") (pintype "passive"))
      (node (ref "R16") (pin "2") (pinfunction "2_2") (pintype "passive"))
      (node (ref "U3") (pin "16") (pinfunction "V33_16") (pintype "power_in"))
    )
    (net (code "93") (name "unconnected-(J3-Pad9)") (class "Default")
      (node (ref "J3") (pin "9") (pinfunction "9_9") (pintype "passive+no_connect"))
    )
    (net (code "94") (name "unconnected-(P7-RFU1-PadA8)") (class "Default")
      (node (ref "P7") (pin "A8") (pinfunction "RFU1_A8") (pintype "bidirectional+no_connect"))
    )
    (net (code "95") (name "unconnected-(P7-RFU1-PadB8)") (class "Default")
      (node (ref "P7") (pin "B8") (pinfunction "RFU1_B8") (pintype "bidirectional+no_connect"))
    )
    (net (code "96") (name "unconnected-(P9-RFU1-PadA8)") (class "Default")
      (node (ref "P9") (pin "A8") (pinfunction "RFU1_A8") (pintype "bidirectional+no_connect"))
    )
    (net (code "97") (name "unconnected-(P9-RFU1-PadB8)") (class "Default")
      (node (ref "P9") (pin "B8") (pinfunction "RFU1_B8") (pintype "bidirectional+no_connect"))
    )
    (net (code "98") (name "unconnected-(S1-A1-Pad4)") (class "Default")
      (node (ref "S1") (pin "4") (pinfunction "A1_4") (pintype "passive"))
    )
    (net (code "99") (name "unconnected-(S1-B0-Pad2)") (class "Default")
      (node (ref "S1") (pin "2") (pinfunction "B0_2") (pintype "passive"))
    )
    (net (code "100") (name "unconnected-(S2-A1-Pad4)") (class "Default")
      (node (ref "S2") (pin "4") (pinfunction "A1_4") (pintype "passive"))
    )
    (net (code "101") (name "unconnected-(S2-B0-Pad2)") (class "Default")
      (node (ref "S2") (pin "2") (pinfunction "B0_2") (pintype "passive"))
    )
    (net (code "102") (name "unconnected-(S3-Pad2)") (class "Default")
      (node (ref "S3") (pin "2") (pinfunction "2_2") (pintype "passive"))
    )
    (net (code "103") (name "unconnected-(U3-P1.5{slash}MOSI{slash}PWM0_{slash}UCC2{slash}AIN5-Pad3)") (class "Default")
      (node (ref "U3") (pin "3") (pinfunction "P1.5/MOSI/PWM0_/UCC2/AIN5_3") (pintype "bidirectional+no_connect"))
    )
    (net (code "104") (name "unconnected-(U3-P2.2{slash}PWM3{slash}INT0_-Pad10)") (class "Default")
      (node (ref "U3") (pin "10") (pinfunction "P2.2/PWM3/INT0__10") (pintype "bidirectional+no_connect"))
    )
    (net (code "105") (name "unconnected-(U3-P2.4{slash}PWM1{slash}T2_{slash}CAP1_-Pad11)") (class "Default")
      (node (ref "U3") (pin "11") (pinfunction "P2.4/PWM1/T2_/CAP1__11") (pintype "bidirectional+no_connect"))
    )
    (net (code "106") (name "unconnected-(U3-P3.4{slash}T0-Pad9)") (class "Default")
      (node (ref "U3") (pin "9") (pinfunction "P3.4/T0_9") (pintype "bidirectional+no_connect"))
    )
    (net (code "107") (name "unconnected-(U3-P5.7{slash}RST-Pad6)") (class "Default")
      (node (ref "U3") (pin "6") (pinfunction "P5.7/RST_6") (pintype "input+no_connect"))
    )
  )
)
